# Enclosure_100x68_PBC-AZ.net
KiCad netlist of a schematic drawn in EAGLE
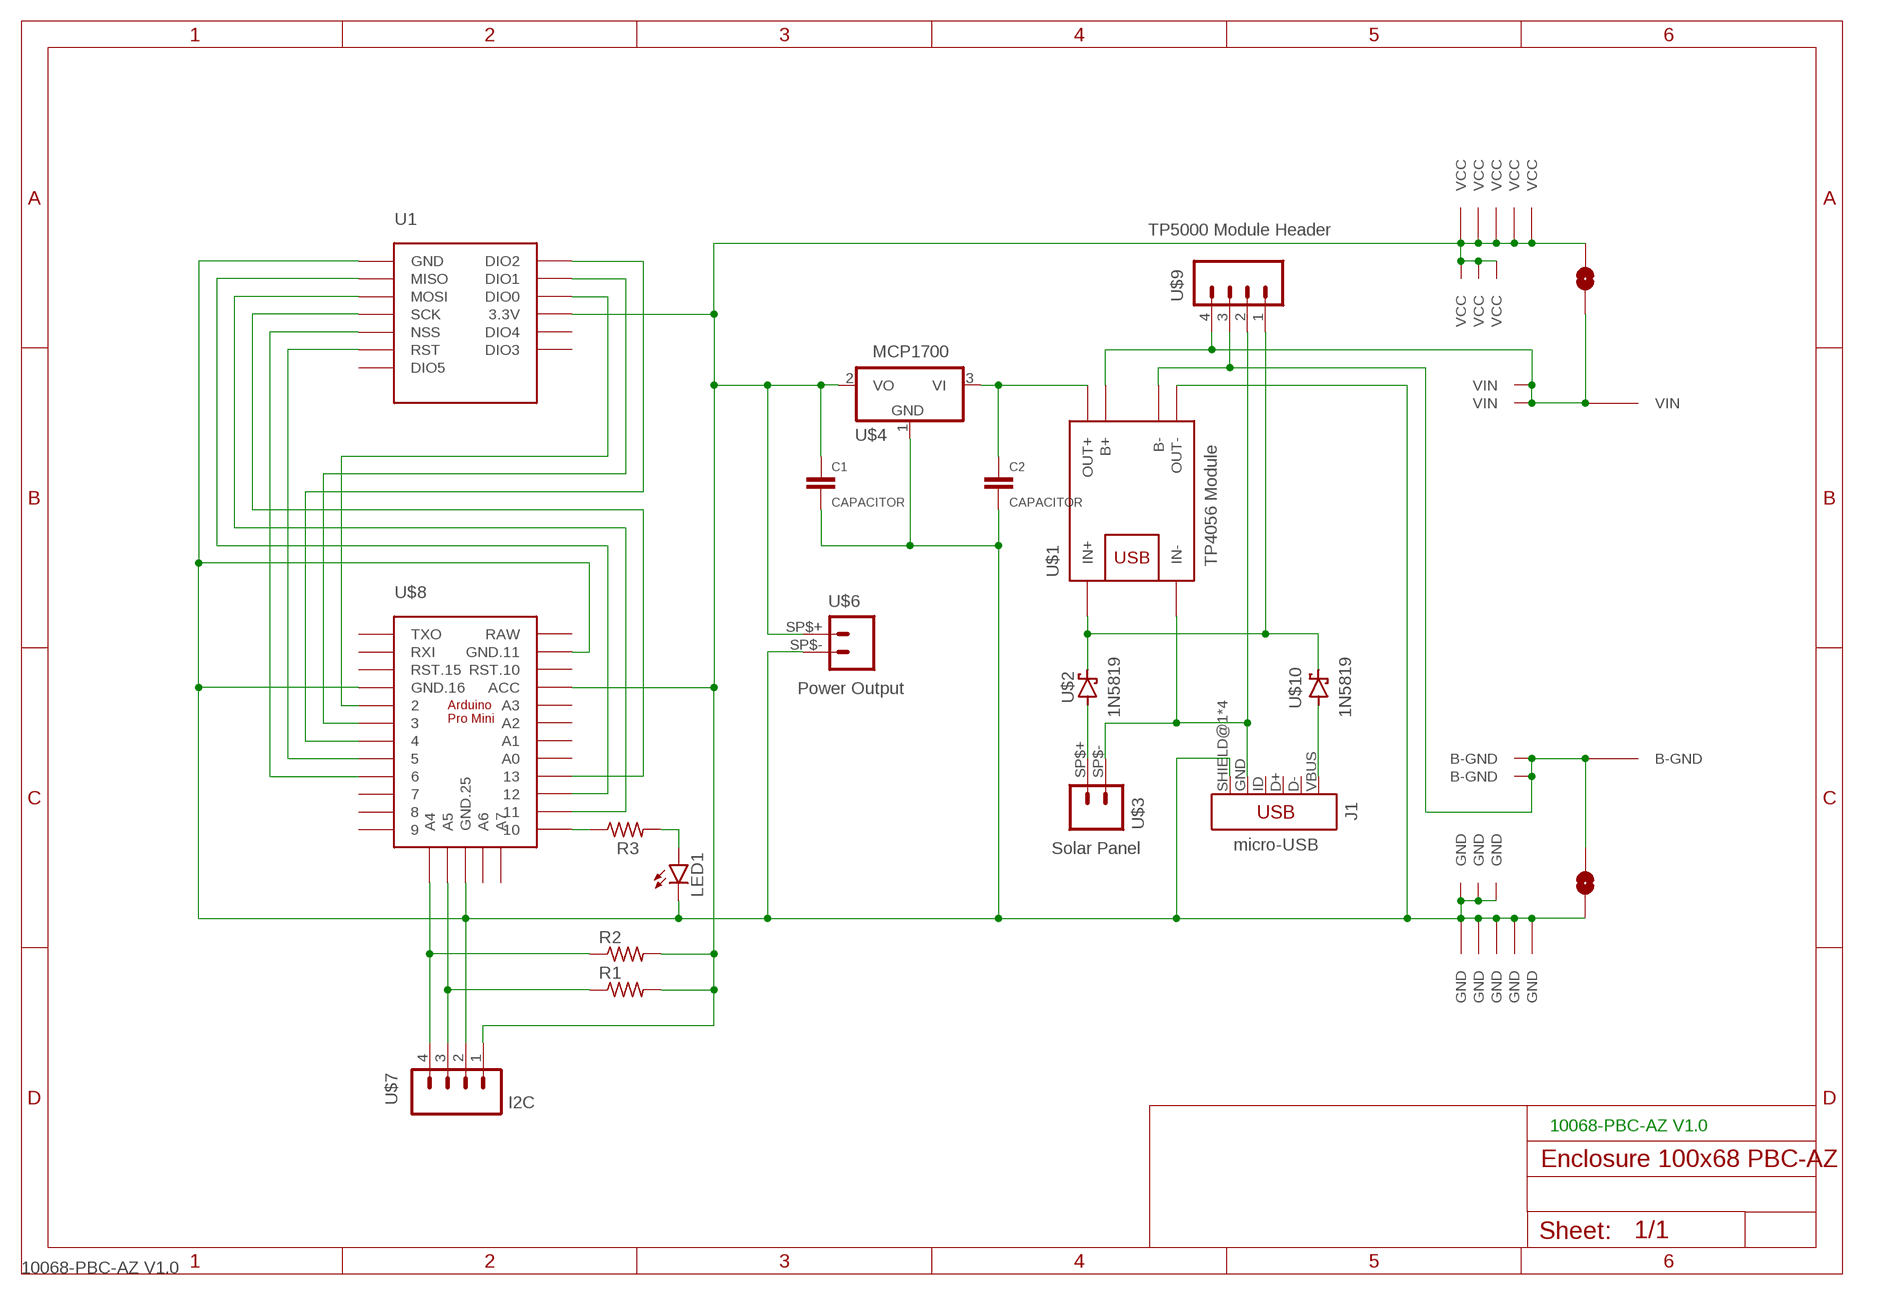
[diagram p0: schematic, sheet 1]

(export (version "E")
  (design (tool "Eeschema 10.0.6"))
  (components
    (comp (ref "C1")
      (value "CAPACITOR")
      (footprint "eagle-import:C0805")
      (libsource (lib "eagle-import") (part "CAPACITOR"))
    )
    (comp (ref "C2")
      (value "CAPACITOR")
      (footprint "eagle-import:C0805")
      (libsource (lib "eagle-import") (part "CAPACITOR"))
    )
    (comp (ref "J1")
      (value "micro-USB")
      (footprint "eagle-import:USB-MINIB")
      (libsource (lib "eagle-import") (part "USB_MINI-B_SMT"))
    )
    (comp (ref "LED1")
      (value "LEDCHIP-LED0805")
      (footprint "eagle-import:CHIP-LED0805")
      (libsource (lib "eagle-import") (part "LEDCHIP-LED0805"))
    )
    (comp (ref "R1")
      (value "RESISTORR0805")
      (footprint "eagle-import:R0805")
      (libsource (lib "eagle-import") (part "RESISTORR0805"))
    )
    (comp (ref "R2")
      (value "RESISTORR0805")
      (footprint "eagle-import:R0805")
      (libsource (lib "eagle-import") (part "RESISTORR0805"))
    )
    (comp (ref "R3")
      (value "RESISTORR0805")
      (footprint "eagle-import:R0805")
      (libsource (lib "eagle-import") (part "RESISTORR0805"))
    )
    (comp (ref "U$1")
      (value "TP4056 Module")
      (footprint "eagle-import:BATTERY-CHARGER-LI-PROT")
      (libsource (lib "eagle-import") (part "BATTERY-CHARGER-LI-PROT"))
    )
    (comp (ref "U$2")
      (value "1N5819")
      (footprint "eagle-import:SOD-123")
      (libsource (lib "eagle-import") (part "1N5819-SOD-123"))
    )
    (comp (ref "U$3")
      (value "Solar Panel")
      (footprint "eagle-import:JST-PH2.0")
      (libsource (lib "eagle-import") (part "JST-PH2.0-MALE"))
    )
    (comp (ref "U$4")
      (value "MCP1700")
      (footprint "eagle-import:SOT23")
      (libsource (lib "eagle-import") (part "MCP1700"))
    )
    (comp (ref "U$5")
      (value "PROTO-34X22-BAT-SJ-CHG-Z")
      (footprint "eagle-import:PROTO-34X22-BAT-SJ-CHG-Z")
      (libsource (lib "eagle-import") (part "PROTO-34X22-BAT-SJ-CHG-Z"))
    )
    (comp (ref "U$6")
      (value "Power Output")
      (footprint "eagle-import:JST-PH1.25")
      (libsource (lib "eagle-import") (part "JST-PH1.25-MALE"))
    )
    (comp (ref "U$7")
      (value "I2C")
      (footprint "eagle-import:CONN_04-GENERIC")
      (libsource (lib "eagle-import") (part "1X4-PIN-HEADER"))
    )
    (comp (ref "U$8")
      (value "ARDUINO-PRO-MINI")
      (footprint "eagle-import:PRO-MINI-29")
      (libsource (lib "eagle-import") (part "ARDUINO-PRO-MINI"))
    )
    (comp (ref "U$9")
      (value "TP5000 Module Header")
      (footprint "eagle-import:CONN_04-GENERIC")
      (libsource (lib "eagle-import") (part "1X4-PIN-HEADER"))
    )
    (comp (ref "U$10")
      (value "1N5819")
      (footprint "eagle-import:SOD-123")
      (libsource (lib "eagle-import") (part "1N5819-SOD-123"))
    )
    (comp (ref "U1")
      (value "RFM95W-PI")
      (footprint "eagle-import:RFM95W-PI")
      (libsource (lib "eagle-import") (part "RFM95W-PI"))
    )
  )
  (nets
    (net (code "1") (name "/RAW") (class "Default")
      (node (ref "U$8") (pin "RAW") (pinfunction "RAW_RAW") (pintype "power_in"))
    )
    (net (code "2") (name "Net-(J1-PadVBUS)") (class "Default")
      (node (ref "J1") (pin "VBUS") (pinfunction "VBUS_VBUS") (pintype "power_in"))
      (node (ref "U$10") (pin "A") (pinfunction "A_A") (pintype "passive"))
    )
    (net (code "3") (name "Net-(LED1-PadA)") (class "Default")
      (node (ref "LED1") (pin "A") (pinfunction "A_A") (pintype "passive"))
      (node (ref "R3") (pin "2") (pinfunction "2_2") (pintype "passive"))
    )
    (net (code "4") (name "Net-(R1-Pad1)") (class "Default")
      (node (ref "R1") (pin "1") (pinfunction "1_1") (pintype "passive"))
      (node (ref "U$7") (pin "3") (pinfunction "3_3") (pintype "passive"))
      (node (ref "U$8") (pin "A5") (pinfunction "A5_A5") (pintype "bidirectional"))
    )
    (net (code "5") (name "Net-(R2-Pad1)") (class "Default")
      (node (ref "R2") (pin "1") (pinfunction "1_1") (pintype "passive"))
      (node (ref "U$7") (pin "4") (pinfunction "4_4") (pintype "passive"))
      (node (ref "U$8") (pin "A4") (pinfunction "A4_A4") (pintype "bidirectional"))
    )
    (net (code "6") (name "Net-(R3-Pad1)") (class "Default")
      (node (ref "R3") (pin "1") (pinfunction "1_1") (pintype "passive"))
      (node (ref "U$8") (pin "10") (pinfunction "10_10") (pintype "bidirectional"))
    )
    (net (code "7") (name "Net-(U$1-PadB+)") (class "Default")
      (node (ref "U$1") (pin "B+") (pinfunction "B+_B+") (pintype "power_in"))
      (node (ref "U$5") (pin "P02-17") (pinfunction "VIN_P02-17") (pintype "power_in"))
      (node (ref "U$5") (pin "P03-16") (pinfunction "VIN_P03-16") (pintype "power_in"))
      (node (ref "U$5") (pin "P06-19") (pinfunction "VIN_P06-19") (pintype "power_in"))
      (node (ref "U$5") (pin "VIN") (pinfunction "VIN_VIN") (pintype "power_in"))
      (node (ref "U$9") (pin "4") (pinfunction "4_4") (pintype "passive"))
    )
    (net (code "8") (name "Net-(U$1-PadB-)") (class "Default")
      (node (ref "U$1") (pin "B-") (pinfunction "B-_B-") (pintype "power_in"))
      (node (ref "U$5") (pin "B-GND") (pinfunction "B-GND_B-GND") (pintype "power_in"))
      (node (ref "U$5") (pin "P28-19") (pinfunction "B-GND_P28-19") (pintype "power_in"))
      (node (ref "U$5") (pin "P32-16") (pinfunction "B-GND_P32-16") (pintype "power_in"))
      (node (ref "U$5") (pin "P33-17") (pinfunction "B-GND_P33-17") (pintype "power_in"))
      (node (ref "U$9") (pin "3") (pinfunction "3_3") (pintype "passive"))
    )
    (net (code "9") (name "Net-(U$1-PadIN+)") (class "Default")
      (node (ref "U$1") (pin "IN+") (pinfunction "IN+_IN+") (pintype "power_in"))
      (node (ref "U$10") (pin "C") (pinfunction "C_C") (pintype "passive"))
      (node (ref "U$2") (pin "C") (pinfunction "C_C") (pintype "passive"))
      (node (ref "U$9") (pin "1") (pinfunction "1_1") (pintype "passive"))
    )
    (net (code "10") (name "Net-(U$3-1)") (class "Default")
      (node (ref "U$2") (pin "A") (pinfunction "A_A") (pintype "passive"))
      (node (ref "U$3") (pin "SP$+") (pinfunction "1_SP$+") (pintype "power_in"))
    )
    (net (code "11") (name "Net-(U$3-2)") (class "Default")
      (node (ref "J1") (pin "GND") (pinfunction "GND_GND") (pintype "power_in"))
      (node (ref "U$1") (pin "IN-") (pinfunction "IN-_IN-") (pintype "power_in"))
      (node (ref "U$3") (pin "SP$-") (pinfunction "2_SP$-") (pintype "power_in"))
      (node (ref "U$9") (pin "2") (pinfunction "2_2") (pintype "passive"))
    )
    (net (code "12") (name "Net-(U$4-GND)") (class "Default")
      (node (ref "C1") (pin "2") (pinfunction "2_2") (pintype "passive"))
      (node (ref "C2") (pin "2") (pinfunction "2_2") (pintype "passive"))
      (node (ref "J1") (pin "SHIELD@1") (pinfunction "SHIELD_SHIELD@1") (pintype "power_in"))
      (node (ref "J1") (pin "SHIELD@2") (pinfunction "SHIELD_SHIELD@2") (pintype "power_in"))
      (node (ref "J1") (pin "SHIELD@3") (pinfunction "SHIELD_SHIELD@3") (pintype "power_in"))
      (node (ref "J1") (pin "SHIELD@4") (pinfunction "SHIELD_SHIELD@4") (pintype "power_in"))
      (node (ref "LED1") (pin "C") (pinfunction "C_C") (pintype "passive"))
      (node (ref "U$1") (pin "OUT-") (pinfunction "OUT-_OUT-") (pintype "power_in"))
      (node (ref "U$4") (pin "1") (pinfunction "GND_1") (pintype "passive"))
      (node (ref "U$5") (pin "GND") (pinfunction "GND_GND") (pintype "power_in"))
      (node (ref "U$5") (pin "P33-13") (pinfunction "GND_P33-13") (pintype "power_in"))
      (node (ref "U$5") (pin "P33-14") (pinfunction "GND_P33-14") (pintype "power_in"))
      (node (ref "U$5") (pin "P33-15") (pinfunction "GND_P33-15") (pintype "power_in"))
      (node (ref "U$5") (pin "P34-13") (pinfunction "GND_P34-13") (pintype "power_in"))
      (node (ref "U$5") (pin "P34-14") (pinfunction "GND_P34-14") (pintype "power_in"))
      (node (ref "U$5") (pin "P34-15") (pinfunction "GND_P34-15") (pintype "power_in"))
      (node (ref "U$5") (pin "P34-16") (pinfunction "GND_P34-16") (pintype "power_in"))
      (node (ref "U$5") (pin "P34-17") (pinfunction "GND_P34-17") (pintype "power_in"))
      (node (ref "U$6") (pin "SP$-") (pinfunction "2_SP$-") (pintype "power_in"))
      (node (ref "U$7") (pin "2") (pinfunction "2_2") (pintype "passive"))
      (node (ref "U$8") (pin "GND@11") (pinfunction "GND.25_GND@11") (pintype "bidirectional"))
      (node (ref "U$8") (pin "GND@16") (pinfunction "GND.16_GND@16") (pintype "power_in"))
      (node (ref "U$8") (pin "GND@25") (pinfunction "GND.11_GND@25") (pintype "power_in"))
      (node (ref "U1") (pin "GND@3") (pinfunction "GND_GND@3") (pintype "power_in"))
      (node (ref "U1") (pin "GND@6") (pinfunction "GND_GND@6") (pintype "power_in"))
    )
    (net (code "13") (name "Net-(U$4-VI)") (class "Default")
      (node (ref "C2") (pin "1") (pinfunction "1_1") (pintype "passive"))
      (node (ref "U$1") (pin "OUT+") (pinfunction "OUT+_OUT+") (pintype "power_in"))
      (node (ref "U$4") (pin "3") (pinfunction "VI_3") (pintype "input"))
    )
    (net (code "14") (name "Net-(U$4-VO)") (class "Default")
      (node (ref "C1") (pin "1") (pinfunction "1_1") (pintype "passive"))
      (node (ref "R1") (pin "2") (pinfunction "2_2") (pintype "passive"))
      (node (ref "R2") (pin "2") (pinfunction "2_2") (pintype "passive"))
      (node (ref "U$4") (pin "2") (pinfunction "VO_2") (pintype "output"))
      (node (ref "U$5") (pin "P01-13") (pinfunction "VCC_P01-13") (pintype "power_in"))
      (node (ref "U$5") (pin "P01-14") (pinfunction "VCC_P01-14") (pintype "power_in"))
      (node (ref "U$5") (pin "P01-15") (pinfunction "VCC_P01-15") (pintype "power_in"))
      (node (ref "U$5") (pin "P01-16") (pinfunction "VCC_P01-16") (pintype "power_in"))
      (node (ref "U$5") (pin "P01-17") (pinfunction "VCC_P01-17") (pintype "power_in"))
      (node (ref "U$5") (pin "P02-13") (pinfunction "VCC_P02-13") (pintype "power_in"))
      (node (ref "U$5") (pin "P02-14") (pinfunction "VCC_P02-14") (pintype "power_in"))
      (node (ref "U$5") (pin "P02-15") (pinfunction "VCC_P02-15") (pintype "power_in"))
      (node (ref "U$5") (pin "VCC") (pinfunction "VCC_VCC") (pintype "power_in"))
      (node (ref "U$6") (pin "SP$+") (pinfunction "1_SP$+") (pintype "power_in"))
      (node (ref "U$7") (pin "1") (pinfunction "1_1") (pintype "passive"))
      (node (ref "U$8") (pin "ACC") (pinfunction "ACC_ACC") (pintype "power_in"))
      (node (ref "U1") (pin "3V3") (pinfunction "3.3V_3V3") (pintype "power_in"))
    )
    (net (code "15") (name "Net-(U$8-Pad2)") (class "Default")
      (node (ref "U$8") (pin "2") (pinfunction "2_2") (pintype "bidirectional"))
      (node (ref "U1") (pin "DIO0") (pinfunction "DIO0_DIO0") (pintype "bidirectional"))
    )
    (net (code "16") (name "Net-(U$8-Pad3)") (class "Default")
      (node (ref "U$8") (pin "3") (pinfunction "3_3") (pintype "bidirectional"))
      (node (ref "U1") (pin "DIO1") (pinfunction "DIO1_DIO1") (pintype "bidirectional"))
    )
    (net (code "17") (name "Net-(U$8-Pad4)") (class "Default")
      (node (ref "U$8") (pin "4") (pinfunction "4_4") (pintype "bidirectional"))
      (node (ref "U1") (pin "DIO2") (pinfunction "DIO2_DIO2") (pintype "bidirectional"))
    )
    (net (code "18") (name "Net-(U$8-Pad5)") (class "Default")
      (node (ref "U$8") (pin "5") (pinfunction "5_5") (pintype "bidirectional"))
      (node (ref "U1") (pin "RST") (pinfunction "RST_RST") (pintype "bidirectional"))
    )
    (net (code "19") (name "Net-(U$8-Pad6)") (class "Default")
      (node (ref "U$8") (pin "6") (pinfunction "6_6") (pintype "bidirectional"))
      (node (ref "U1") (pin "NSS") (pinfunction "NSS_NSS") (pintype "bidirectional"))
    )
    (net (code "20") (name "Net-(U$8-Pad11)") (class "Default")
      (node (ref "U$8") (pin "11") (pinfunction "11_11") (pintype "bidirectional"))
      (node (ref "U1") (pin "MOSI") (pinfunction "MOSI_MOSI") (pintype "bidirectional"))
    )
    (net (code "21") (name "Net-(U$8-Pad12)") (class "Default")
      (node (ref "U$8") (pin "12") (pinfunction "12_12") (pintype "bidirectional"))
      (node (ref "U1") (pin "MISO") (pinfunction "MISO_MISO") (pintype "bidirectional"))
    )
    (net (code "22") (name "Net-(U$8-Pad13)") (class "Default")
      (node (ref "U$8") (pin "13") (pinfunction "13_13") (pintype "bidirectional"))
      (node (ref "U1") (pin "SCK") (pinfunction "SCK_SCK") (pintype "bidirectional"))
    )
    (net (code "23") (name "unconnected-(J1-PadD+)") (class "Default")
      (node (ref "J1") (pin "D+") (pinfunction "D+_D+") (pintype "bidirectional"))
    )
    (net (code "24") (name "unconnected-(J1-PadD-)") (class "Default")
      (node (ref "J1") (pin "D-") (pinfunction "D-_D-") (pintype "bidirectional"))
    )
    (net (code "25") (name "unconnected-(J1-PadID)") (class "Default")
      (node (ref "J1") (pin "ID") (pinfunction "ID_ID") (pintype "bidirectional"))
    )
    (net (code "26") (name "unconnected-(U$8-Pad7)") (class "Default")
      (node (ref "U$8") (pin "7") (pinfunction "7_7") (pintype "bidirectional"))
    )
    (net (code "27") (name "unconnected-(U$8-Pad8)") (class "Default")
      (node (ref "U$8") (pin "8") (pinfunction "8_8") (pintype "bidirectional"))
    )
    (net (code "28") (name "unconnected-(U$8-Pad9)") (class "Default")
      (node (ref "U$8") (pin "9") (pinfunction "9_9") (pintype "bidirectional"))
    )
    (net (code "29") (name "unconnected-(U$8-PadA0)") (class "Default")
      (node (ref "U$8") (pin "A0") (pinfunction "A0_A0") (pintype "bidirectional"))
    )
    (net (code "30") (name "unconnected-(U$8-PadA1)") (class "Default")
      (node (ref "U$8") (pin "A1") (pinfunction "A1_A1") (pintype "bidirectional"))
    )
    (net (code "31") (name "unconnected-(U$8-PadA2)") (class "Default")
      (node (ref "U$8") (pin "A2") (pinfunction "A2_A2") (pintype "bidirectional"))
    )
    (net (code "32") (name "unconnected-(U$8-PadA3)") (class "Default")
      (node (ref "U$8") (pin "A3") (pinfunction "A3_A3") (pintype "bidirectional"))
    )
    (net (code "33") (name "unconnected-(U$8-PadA6)") (class "Default")
      (node (ref "U$8") (pin "A6") (pinfunction "A6_A6") (pintype "bidirectional"))
    )
    (net (code "34") (name "unconnected-(U$8-PadA7)") (class "Default")
      (node (ref "U$8") (pin "A7") (pinfunction "A7_A7") (pintype "bidirectional"))
    )
    (net (code "35") (name "unconnected-(U$8-PadRXI)") (class "Default")
      (node (ref "U$8") (pin "RXI") (pinfunction "RXI_RXI") (pintype "input"))
    )
    (net (code "36") (name "unconnected-(U$8-PadTXO)") (class "Default")
      (node (ref "U$8") (pin "TXO") (pinfunction "TXO_TXO") (pintype "bidirectional"))
    )
    (net (code "37") (name "unconnected-(U$8-RST.10-PadRST@10)") (class "Default")
      (node (ref "U$8") (pin "RST@10") (pinfunction "RST.10_RST@10") (pintype "input"))
    )
    (net (code "38") (name "unconnected-(U$8-RST.15-PadRST@15)") (class "Default")
      (node (ref "U$8") (pin "RST@15") (pinfunction "RST.15_RST@15") (pintype "input"))
    )
    (net (code "39") (name "unconnected-(U1-PadDIO3)") (class "Default")
      (node (ref "U1") (pin "DIO3") (pinfunction "DIO3_DIO3") (pintype "bidirectional"))
    )
    (net (code "40") (name "unconnected-(U1-PadDIO4)") (class "Default")
      (node (ref "U1") (pin "DIO4") (pinfunction "DIO4_DIO4") (pintype "bidirectional"))
    )
    (net (code "41") (name "unconnected-(U1-PadDIO5)") (class "Default")
      (node (ref "U1") (pin "DIO5") (pinfunction "DIO5_DIO5") (pintype "bidirectional"))
    )
  )
)
